# ppg_reconstruct.net
KiCad netlist of a schematic drawn in Altium Designer
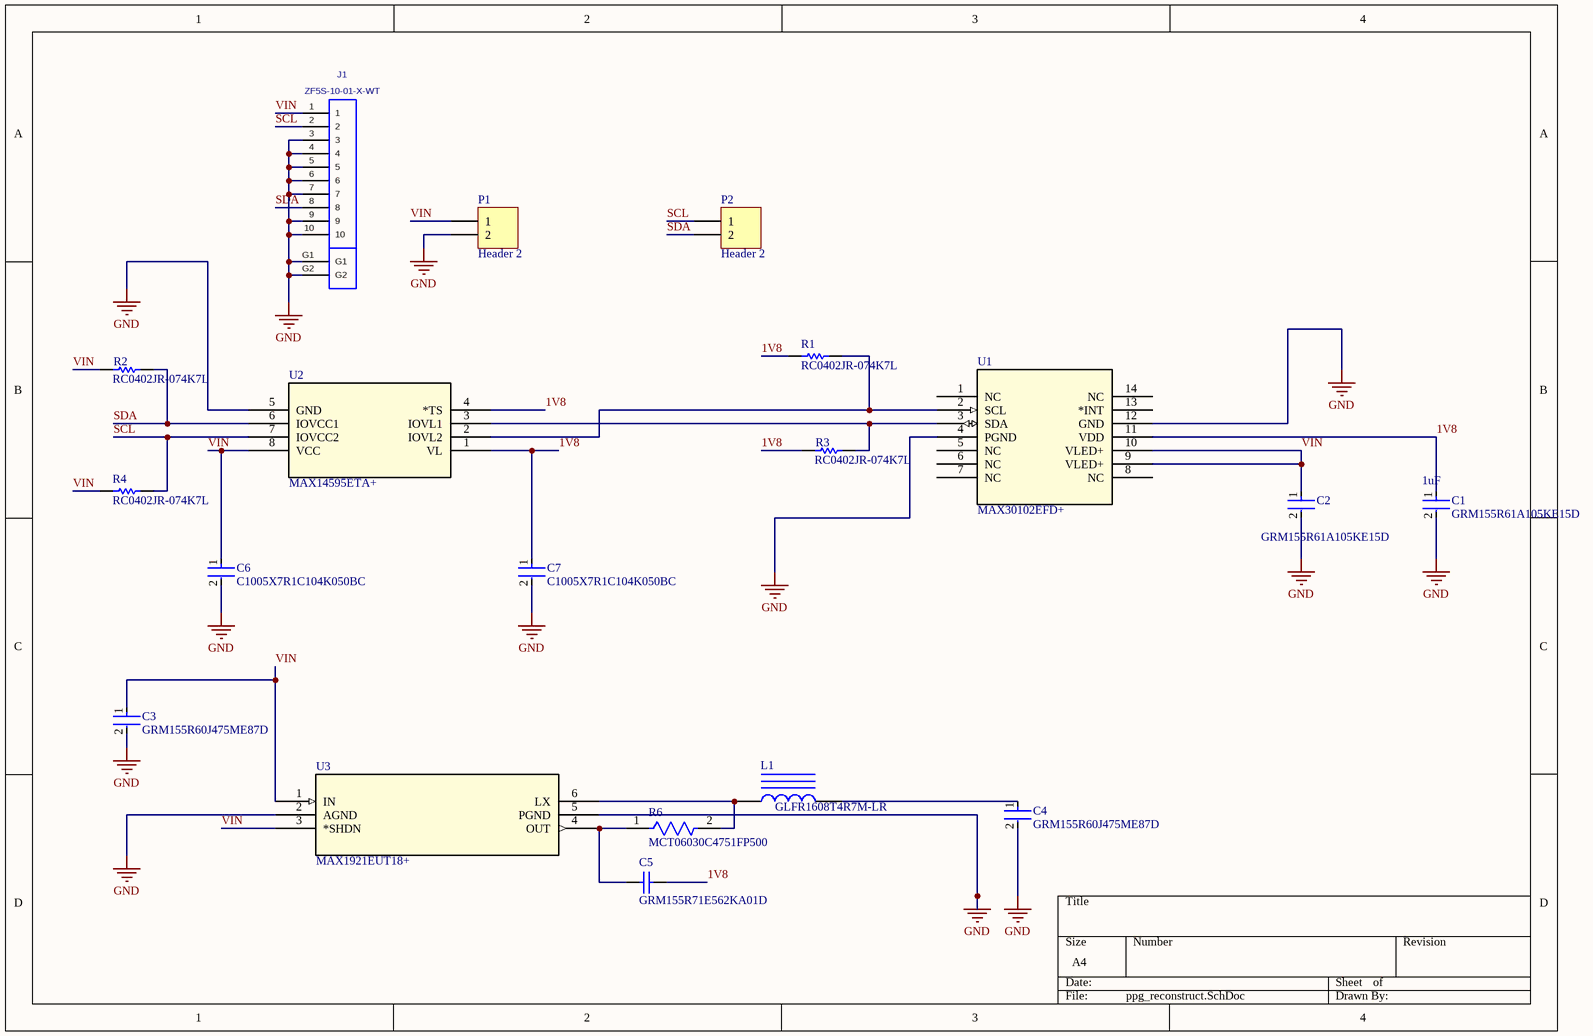
[diagram p0: ppg_reconstruct.SchDoc]

(export (version "E")
  (design (tool "Eeschema 10.0.6"))
  (components
    (comp (ref "C1")
      (value "GRM155R61A105KE15D")
      (footprint "FP-GRM15-0_1-MFG")
      (description "CAP CER 1UF 10V X5R 0402")
      (fields
        (field (name "OCTOPART") "https://octopart.com/grm155r61a105ke15d-murata-197442")
        (field (name "MANUFACTURER") "Murata")
        (field (name "ALTIUM_VALUE") "1uF")
      )
      (libsource (lib "Altium Content Vault") (part "02cd4be3c70576c341d710602a673aa"))
    )
    (comp (ref "C2")
      (value "GRM155R61A105KE15D")
      (footprint "FP-GRM15-0_1-MFG")
      (description "CAP CER 1UF 10V X5R 0402")
      (fields
        (field (name "OCTOPART") "https://octopart.com/grm155r61a105ke15d-murata-197442")
        (field (name "MANUFACTURER") "Murata")
      )
      (libsource (lib "Altium Content Vault") (part "02cd4be3c70576c341d710602a673aa"))
    )
    (comp (ref "C3")
      (value "GRM155R60J475ME87D")
      (footprint "FP-GRM155-0_15-MFG")
      (description "Chip Multilayer Ceramic Capacitors for General Purpose, 0402, 4.7uF, X5R, 15%, 20%, 6.3V")
      (fields (field (name "TOLERANCE") "20%") (field (name "VOLTAGE") "6.3V"))
      (libsource (lib "Altium Content Vault") (part "b4654b650e69147ec39a6b967a45e02"))
    )
    (comp (ref "C4")
      (value "GRM155R60J475ME87D")
      (footprint "FP-GRM155-0_15-MFG")
      (description "Chip Multilayer Ceramic Capacitors for General Purpose, 0402, 4.7uF, X5R, 15%, 20%, 6.3V")
      (fields (field (name "TOLERANCE") "20%") (field (name "VOLTAGE") "6.3V"))
      (libsource (lib "Altium Content Vault") (part "b4654b650e69147ec39a6b967a45e02"))
    )
    (comp (ref "C5")
      (value "GRM155R71E562KA01D")
      (footprint "CAPC1005X55X25ML05T10")
      (fields (field (name "MANUFACTURER") "Murata"))
      (libsource (lib "Altium Content Vault") (part "CAP"))
    )
    (comp (ref "C6")
      (value "C1005X7R1C104K050BC")
      (footprint "FP-C1005-050-0_05-MFG")
      (description "Multilayer Ceramic Capacitors 100nF ±10% 16V X7R SMD 0402")
      (fields (field (name "VOLTAGE") "16V") (field (name "TOLERANCE") "10%"))
      (libsource (lib "Altium Content Vault") (part "b4654b650e69147ec39a6b967a45e02"))
    )
    (comp (ref "C7")
      (value "C1005X7R1C104K050BC")
      (footprint "FP-C1005-050-0_05-MFG")
      (description "Multilayer Ceramic Capacitors 100nF ±10% 16V X7R SMD 0402")
      (fields (field (name "VOLTAGE") "16V") (field (name "TOLERANCE") "10%"))
      (libsource (lib "Altium Content Vault") (part "b4654b650e69147ec39a6b967a45e02"))
    )
    (comp (ref "J1")
      (value "ZF5S-10-01-X-WT")
      (footprint "ZF5S-10-01-X-WT")
      (description "ZERO INSERTION FORCE 0.5MM ASSEMBLY, 01 LEAD STYLE.")
      (fields (field (name "MANUFACTURER") "SAMTEC") (field (name "CREATED") "January 30, 2015 - Wendy Xin"))
      (libsource (lib "ZF5S-10-01-X-WT--Symbol-Altium-44987") (part "ZF5S-10-01-X-WT"))
    )
    (comp (ref "L1")
      (value "GLFR1608T4R7M-LR")
      (footprint "INDC1608X100X35LL20T15")
      (description "Chip Inductor, 4.7 uH, +/- 20%, -40 to 105 degC, 0603 (1608 Metric), RoHS, Tape and Reel")
      (fields (field (name "MANUFACTURER") "TDK") (field (name "TOLERANCE") "±20%"))
      (libsource (lib "Altium Content Vault") (part "IND-DOT-2_A"))
    )
    (comp (ref "P1")
      (value "Header 2")
      (footprint "HDR1X2")
      (description "Header, 2-Pin")
      (fields (field (name "PUBLISHER") "Altium Limited"))
      (libsource (lib "Miscellaneous Connectors") (part "Header 2"))
    )
    (comp (ref "P2")
      (value "Header 2")
      (footprint "HDR1X2")
      (description "Header, 2-Pin")
      (fields (field (name "PUBLISHER") "Altium Limited"))
      (libsource (lib "Miscellaneous Connectors") (part "Header 2"))
    )
    (comp (ref "R1")
      (value "RC0402JR-074K7L")
      (footprint "RESC1005X40X25LL05T10")
      (fields (field (name "MANUFACTURER") "Yageo / Phycomp"))
      (libsource (lib "Altium Content Vault") (part "RES"))
    )
    (comp (ref "R2")
      (value "RC0402JR-074K7L")
      (footprint "RESC1005X40X25LL05T10")
      (fields (field (name "MANUFACTURER") "Yageo / Phycomp"))
      (libsource (lib "Altium Content Vault") (part "RES"))
    )
    (comp (ref "R3")
      (value "RC0402JR-074K7L")
      (footprint "RESC1005X40X25LL05T10")
      (fields (field (name "MANUFACTURER") "Yageo / Phycomp"))
      (libsource (lib "Altium Content Vault") (part "RES"))
    )
    (comp (ref "R4")
      (value "RC0402JR-074K7L")
      (footprint "RESC1005X40X25LL05T10")
      (fields (field (name "MANUFACTURER") "Yageo / Phycomp"))
      (libsource (lib "Altium Content Vault") (part "RES"))
    )
    (comp (ref "R6")
      (value "MCT06030C4751FP500")
      (footprint "FP-MCT0603-IPC_A")
      (description "RES SMD 100 OHM 1% 1/8W 0603")
      (fields (field (name "TOLERANCE") "1%"))
      (libsource (lib "Altium Content Vault") (part "1029c3af85768c4190bb7ad29bc67b5"))
    )
    (comp (ref "U1")
      (value "MAX30102EFD+")
      (footprint "21-1048_F143A5+1_MXM")
      (description "No Description Available")
      (fields (field (name "COPYRIGHT") "Copyright (C) 2023 Ultra Librarian. All rights reserved."))
      (libsource (lib "MAX30102EFD&plus_") (part "MAX30102EFD+"))
    )
    (comp (ref "U2")
      (value "MAX14595ETA+")
      (footprint "21-0487_T822CN+1_MXM")
      (description "No Description Available")
      (fields (field (name "COPYRIGHT") "Copyright (C) 2023 Ultra Librarian. All rights reserved."))
      (libsource (lib "MAX14595ETA&plus_") (part "MAX14595ETA+"))
    )
    (comp (ref "U3")
      (value "MAX1921EUT18+")
      (footprint "21-0058I_MXM")
      (description "No Description Available")
      (fields (field (name "COPYRIGHT") "Copyright (C) 2023 Ultra Librarian. All rights reserved."))
      (libsource (lib "MAX1921EUT18&plus_") (part "MAX1921EUT18+"))
    )
  )
  (nets
    (net (code "1") (name "/1V8") (class "Default")
      (node (ref "C1") (pin "1") (pinfunction "1_1") (pintype "passive"))
      (node (ref "C5") (pin "2") (pinfunction "2_2") (pintype "passive"))
      (node (ref "C7") (pin "1") (pinfunction "1_1") (pintype "passive"))
      (node (ref "R1") (pin "1") (pinfunction "1_1") (pintype "passive"))
      (node (ref "R3") (pin "1") (pinfunction "1_1") (pintype "passive"))
      (node (ref "U1") (pin "11") (pinfunction "VDD_11") (pintype "power_in"))
      (node (ref "U2") (pin "1") (pinfunction "VL_1") (pintype "power_in"))
      (node (ref "U2") (pin "4") (pinfunction "*TS_4") (pintype "passive"))
    )
    (net (code "2") (name "/SCL") (class "Default")
      (node (ref "J1") (pin "2") (pinfunction "2_2") (pintype "passive"))
      (node (ref "P2") (pin "1") (pinfunction "1_1") (pintype "passive"))
      (node (ref "R4") (pin "2") (pinfunction "2_2") (pintype "passive"))
      (node (ref "U2") (pin "7") (pinfunction "IOVCC2_7") (pintype "passive"))
    )
    (net (code "3") (name "/SDA") (class "Default")
      (node (ref "J1") (pin "8") (pinfunction "8_8") (pintype "passive"))
      (node (ref "P2") (pin "2") (pinfunction "2_2") (pintype "passive"))
      (node (ref "R2") (pin "2") (pinfunction "2_2") (pintype "passive"))
      (node (ref "U2") (pin "6") (pinfunction "IOVCC1_6") (pintype "passive"))
    )
    (net (code "4") (name "/VIN") (class "Default")
      (node (ref "C2") (pin "1") (pinfunction "1_1") (pintype "passive"))
      (node (ref "C3") (pin "1") (pinfunction "1_1") (pintype "passive"))
      (node (ref "C6") (pin "1") (pinfunction "1_1") (pintype "passive"))
      (node (ref "J1") (pin "1") (pinfunction "1_1") (pintype "passive"))
      (node (ref "P1") (pin "1") (pinfunction "1_1") (pintype "passive"))
      (node (ref "R2") (pin "1") (pinfunction "1_1") (pintype "passive"))
      (node (ref "R4") (pin "1") (pinfunction "1_1") (pintype "passive"))
      (node (ref "U1") (pin "10") (pinfunction "VLED+_10") (pintype "passive"))
      (node (ref "U1") (pin "9") (pinfunction "VLED+_9") (pintype "passive"))
      (node (ref "U2") (pin "8") (pinfunction "VCC_8") (pintype "power_in"))
      (node (ref "U3") (pin "1") (pinfunction "IN_1") (pintype "input"))
      (node (ref "U3") (pin "3") (pinfunction "*SHDN_3") (pintype "passive"))
    )
    (net (code "5") (name "GND") (class "Default")
      (node (ref "C1") (pin "2") (pinfunction "2_2") (pintype "passive"))
      (node (ref "C2") (pin "2") (pinfunction "2_2") (pintype "passive"))
      (node (ref "C3") (pin "2") (pinfunction "2_2") (pintype "passive"))
      (node (ref "C4") (pin "2") (pinfunction "2_2") (pintype "passive"))
      (node (ref "C6") (pin "2") (pinfunction "2_2") (pintype "passive"))
      (node (ref "C7") (pin "2") (pinfunction "2_2") (pintype "passive"))
      (node (ref "J1") (pin "10") (pinfunction "10_10") (pintype "passive"))
      (node (ref "J1") (pin "3") (pinfunction "3_3") (pintype "passive"))
      (node (ref "J1") (pin "4") (pinfunction "4_4") (pintype "passive"))
      (node (ref "J1") (pin "5") (pinfunction "5_5") (pintype "passive"))
      (node (ref "J1") (pin "6") (pinfunction "6_6") (pintype "passive"))
      (node (ref "J1") (pin "7") (pinfunction "7_7") (pintype "passive"))
      (node (ref "J1") (pin "9") (pinfunction "9_9") (pintype "passive"))
      (node (ref "J1") (pin "G1") (pinfunction "G1_G1") (pintype "passive"))
      (node (ref "J1") (pin "G2") (pinfunction "G2_G2") (pintype "passive"))
      (node (ref "P1") (pin "2") (pinfunction "2_2") (pintype "passive"))
      (node (ref "U1") (pin "12") (pinfunction "GND_12") (pintype "power_in"))
      (node (ref "U1") (pin "4") (pinfunction "PGND_4") (pintype "power_in"))
      (node (ref "U2") (pin "5") (pinfunction "GND_5") (pintype "power_in"))
      (node (ref "U3") (pin "2") (pinfunction "AGND_2") (pintype "power_in"))
      (node (ref "U3") (pin "5") (pinfunction "PGND_5") (pintype "power_in"))
    )
    (net (code "6") (name "Net-(C4-Pad1)") (class "Default")
      (node (ref "C4") (pin "1") (pinfunction "1_1") (pintype "passive"))
      (node (ref "L1") (pin "2") (pinfunction "2_2") (pintype "passive"))
    )
    (net (code "7") (name "Net-(U1-SCL)") (class "Default")
      (node (ref "R1") (pin "2") (pinfunction "2_2") (pintype "passive"))
      (node (ref "U1") (pin "2") (pinfunction "SCL_2") (pintype "input"))
      (node (ref "U2") (pin "2") (pinfunction "IOVL2_2") (pintype "passive"))
    )
    (net (code "8") (name "Net-(U1-SDA)") (class "Default")
      (node (ref "R3") (pin "2") (pinfunction "2_2") (pintype "passive"))
      (node (ref "U1") (pin "3") (pinfunction "SDA_3") (pintype "bidirectional"))
      (node (ref "U2") (pin "3") (pinfunction "IOVL1_3") (pintype "passive"))
    )
    (net (code "9") (name "Net-(U3-LX)") (class "Default")
      (node (ref "L1") (pin "1") (pinfunction "1_1") (pintype "passive"))
      (node (ref "R6") (pin "2") (pinfunction "2_2") (pintype "passive"))
      (node (ref "U3") (pin "6") (pinfunction "LX_6") (pintype "passive"))
    )
    (net (code "10") (name "Net-(U3-OUT)") (class "Default")
      (node (ref "C5") (pin "1") (pinfunction "1_1") (pintype "passive"))
      (node (ref "R6") (pin "1") (pinfunction "1_1") (pintype "passive"))
      (node (ref "U3") (pin "4") (pinfunction "OUT_4") (pintype "output"))
    )
    (net (code "11") (name "unconnected-(U1-*INT-Pad13)") (class "Default")
      (node (ref "U1") (pin "13") (pinfunction "*INT_13") (pintype "passive"))
    )
    (net (code "12") (name "unconnected-(U1-NC-Pad1)") (class "Default")
      (node (ref "U1") (pin "1") (pinfunction "NC_1") (pintype "passive"))
    )
    (net (code "13") (name "unconnected-(U1-NC-Pad5)") (class "Default")
      (node (ref "U1") (pin "5") (pinfunction "NC_5") (pintype "passive"))
    )
    (net (code "14") (name "unconnected-(U1-NC-Pad6)") (class "Default")
      (node (ref "U1") (pin "6") (pinfunction "NC_6") (pintype "passive"))
    )
    (net (code "15") (name "unconnected-(U1-NC-Pad7)") (class "Default")
      (node (ref "U1") (pin "7") (pinfunction "NC_7") (pintype "passive"))
    )
    (net (code "16") (name "unconnected-(U1-NC-Pad8)") (class "Default")
      (node (ref "U1") (pin "8") (pinfunction "NC_8") (pintype "passive"))
    )
    (net (code "17") (name "unconnected-(U1-NC-Pad14)") (class "Default")
      (node (ref "U1") (pin "14") (pinfunction "NC_14") (pintype "passive"))
    )
  )
)
